# Acoustics_Board_Power.net
KiCad netlist of a schematic drawn in Altium Designer
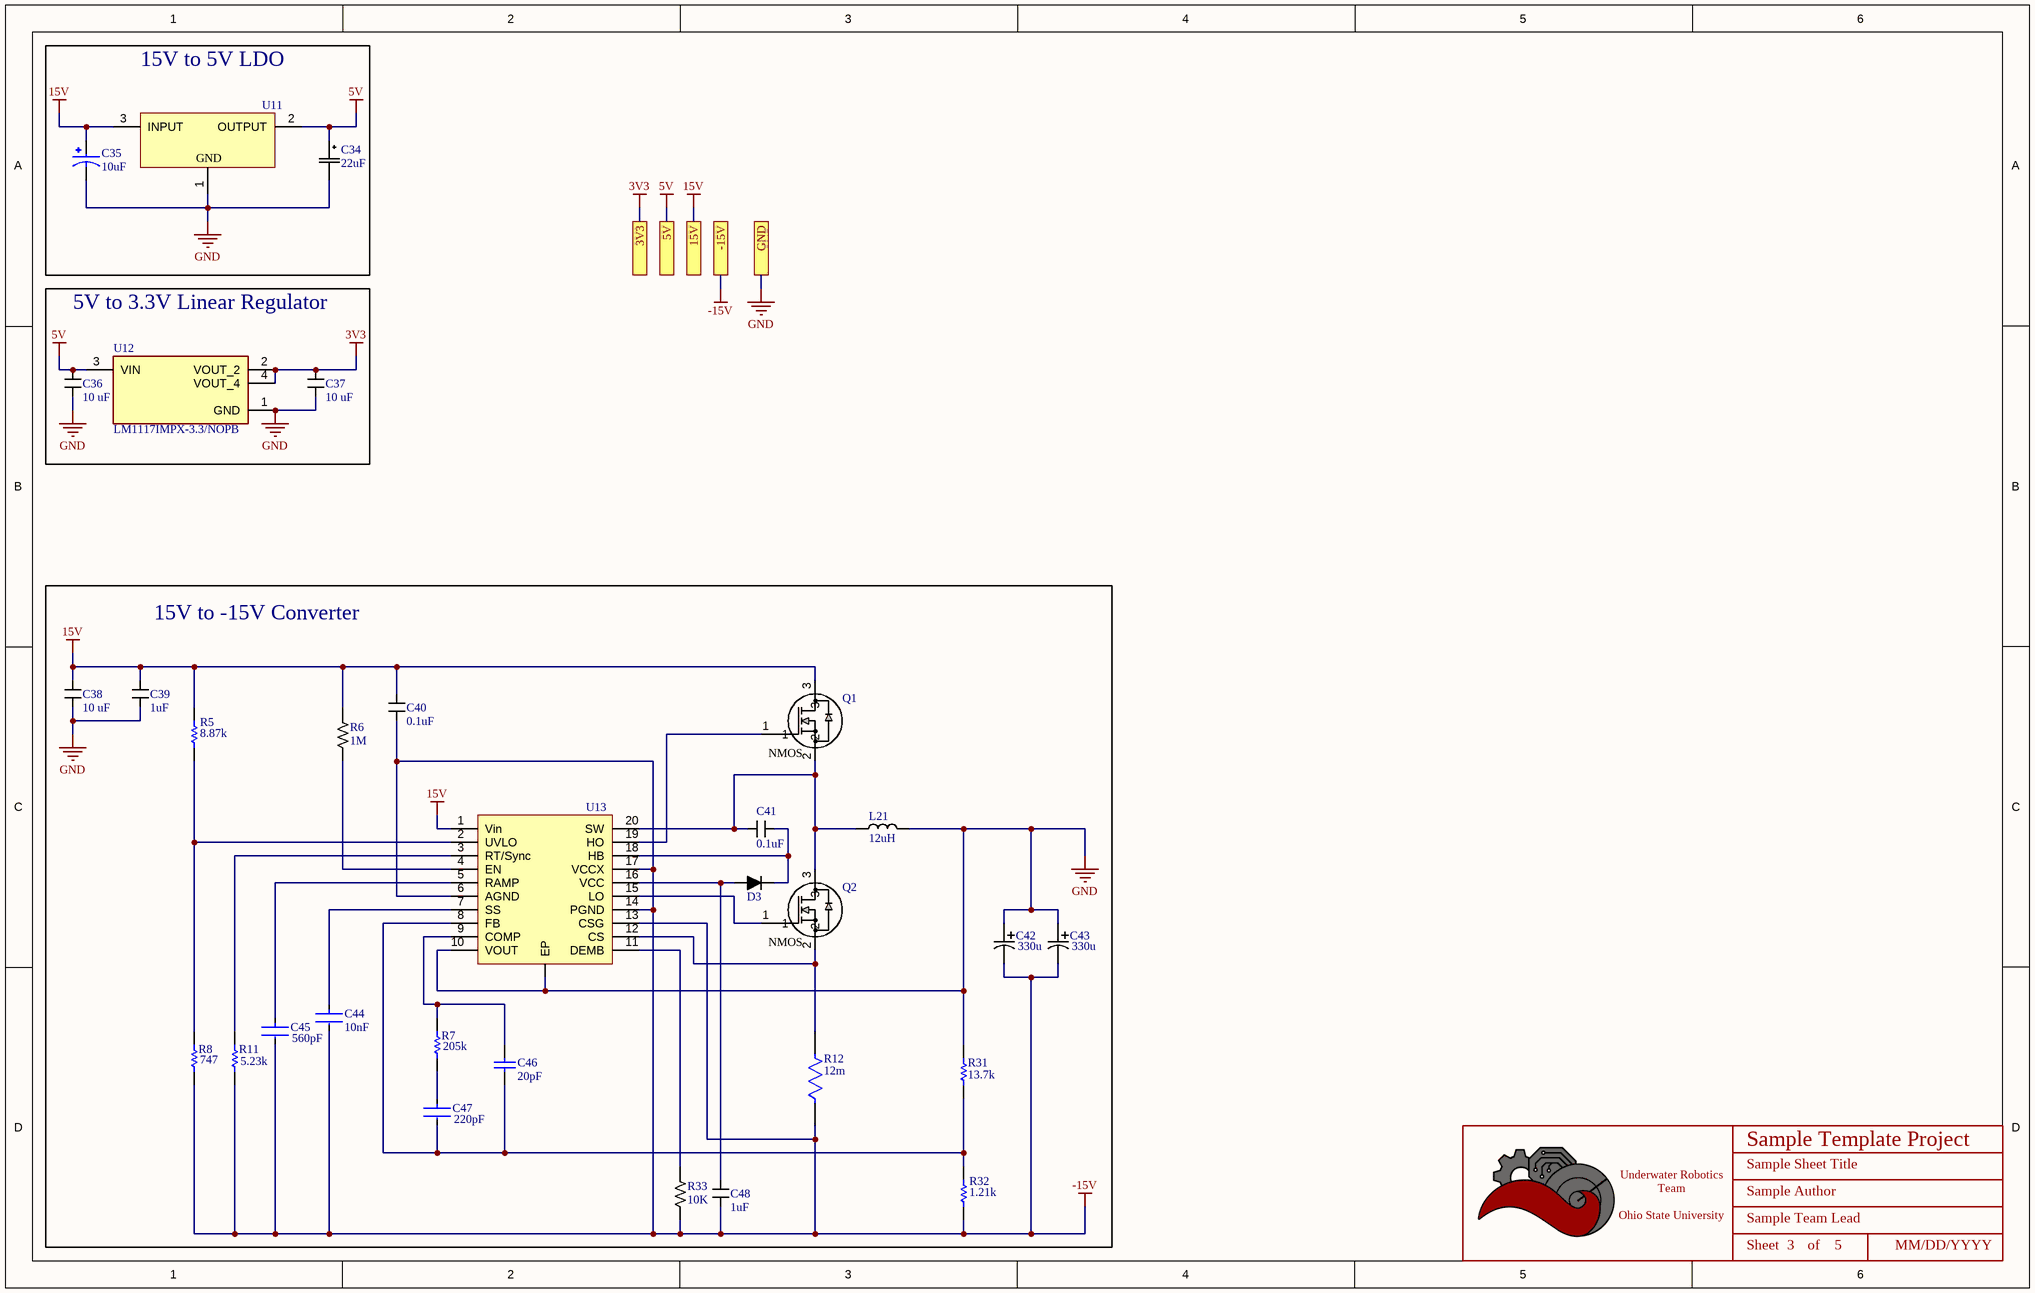
[diagram p0: Acoustics Board Power.SchDoc]

(export (version "E")
  (design (tool "Eeschema 10.0.6"))
  (components
    (comp (ref "C34")
      (value "22uF")
      (footprint "PCAP_8x5.4-ELECT_NCA")
      (description "22 µF 35 V Aluminum Electrolytic Capacitors Radial, Can - SMD 1000 Hrs")
      (fields
        (field (name "VOLTAGE") "35V")
        (field (name "Comment") "22uF electrolytic 35 V")
        (field (name "MADE BY") "Robert Pafford")
      )
      (libsource (lib "Capacitors") (part "CAP ALUM 22UF 20% 35V SMD"))
    )
    (comp (ref "C35")
      (value "10uF")
      (footprint "CAP_EEHZC1J100P")
      (description "10 µF 63 V Aluminum - Polymer Capacitors Radial, Can SMD 120mOhm")
      (fields
        (field (name "TOLERANCE") "+/- 20%")
        (field (name "Comment") "10uF electrolytic 63V")
        (field (name "MADE BY") "Robert Pafford")
      )
      (libsource (lib "Capacitors") (part "CAP ALUM 10UF 20% 63V SMD"))
    )
    (comp (ref "C36")
      (value "10uF Ceramic 6.3V")
      (footprint "CAPACITOR_0603")
      (description "Cap 10uF 6.3V +/-20%\r\nCeramic 0603")
      (fields
        (field (name "TOLERANCE") "+/- 20%")
        (field (name "VOLTAGE") "6.3V")
        (field (name "VALUE (UF)") "10 uF")
        (field (name "MADE BY") "Flip B")
      )
      (libsource (lib "Capacitors") (part "CAPACITOR_10uF_0603"))
    )
    (comp (ref "C37")
      (value "10uF Ceramic 6.3V")
      (footprint "CAPACITOR_0603")
      (description "Cap 10uF 6.3V +/-20%\r\nCeramic 0603")
      (fields
        (field (name "TOLERANCE") "+/- 20%")
        (field (name "VOLTAGE") "6.3V")
        (field (name "VALUE (UF)") "10 uF")
        (field (name "MADE BY") "Flip B")
      )
      (libsource (lib "Capacitors") (part "CAPACITOR_10uF_0603"))
    )
    (comp (ref "C38")
      (value "10uF Ceramic 6.3V")
      (footprint "CAPACITOR_0603")
      (description "Cap 10uF 6.3V +/-20%\r\nCeramic 0603")
      (fields
        (field (name "TOLERANCE") "+/- 20%")
        (field (name "VOLTAGE") "6.3V")
        (field (name "VALUE (UF)") "10 uF")
        (field (name "MADE BY") "Flip B")
      )
      (libsource (lib "Capacitors") (part "CAPACITOR_10uF_0603"))
    )
    (comp (ref "C39")
      (value "1uF")
      (footprint "CAPACITOR_0402")
      (description "Cap 1uF 16V +/-10%\r\nCeramic 0402")
      (fields
        (field (name "TOLERANCE") "+/- 10%")
        (field (name "VOLTAGE") "16V")
        (field (name "MADE BY") "Robert Pafford")
      )
      (libsource (lib "Capacitors") (part "CAPACITOR_1uF_0402"))
    )
    (comp (ref "C40")
      (value "0.1uF")
      (footprint "CAPACITOR_0402")
      (description "Cap 100nF 25V +/-10%\r\nCeramic 0402")
      (fields
        (field (name "TOLERANCE") "+/- 10%")
        (field (name "VOLTAGE") "25V")
        (field (name "MADE BY") "Robert Pafford")
      )
      (libsource (lib "Capacitors") (part "CAPACITOR_0.1uF_0402"))
    )
    (comp (ref "C41")
      (value "0.1uF")
      (footprint "CAPACITOR_0402")
      (description "Cap 100nF 25V +/-10%\r\nCeramic 0402")
      (fields
        (field (name "TOLERANCE") "+/- 10%")
        (field (name "VOLTAGE") "25V")
        (field (name "MADE BY") "Robert Pafford")
      )
      (libsource (lib "Capacitors") (part "CAPACITOR_0.1uF_0402"))
    )
    (comp (ref "C42")
      (value "EEH-ZC1E331P")
      (footprint "PCAP_EEHZ_G_PAN")
      (description "No Description Available")
      (fields
        (field (name "CAPACITANCE") "330u")
        (field (name "COPYRIGHT") "Copyright (C) 2024 Ultra Librarian. All rights reserved.")
      )
      (libsource (lib "Capacitors") (part "EEH-ZC1E331P"))
    )
    (comp (ref "C43")
      (value "EEH-ZC1E331P")
      (footprint "PCAP_EEHZ_G_PAN")
      (description "No Description Available")
      (fields
        (field (name "CAPACITANCE") "330u")
        (field (name "COPYRIGHT") "Copyright (C) 2024 Ultra Librarian. All rights reserved.")
      )
      (libsource (lib "Capacitors") (part "EEH-ZC1E331P"))
    )
    (comp (ref "C44")
      (value "10nF")
      (footprint "CAPACITOR_0402")
      (description "CAP CER 10000PF 50V X7R 0402")
      (fields
        (field (name "OCTOPART") "https://octopart.com/cc0402krx7r9bb103-yageo-8376513")
        (field (name "MANUFACTURER PART NUMBER") "CC0402KRX7R9BB103")
      )
      (libsource (lib "Capacitors") (part "CAP CER 0.01 UF 0402"))
    )
    (comp (ref "C45")
      (value "CL10C221JB8NNNC")
      (footprint "FP-CL10-IPC_C")
      (description "Cap Ceramic 220pF 50V C0G ±5% Pad SMD 0603 +125°C T/R")
      (fields
        (field (name "VOLTAGE") "50V")
        (field (name "CAPACITANCE") "560pF")
        (field (name "TOLERANCE") "5%")
      )
      (libsource (lib "Altium Content Vault") (part "b4654b650e69147ec39a6b967a45e02"))
    )
    (comp (ref "C46")
      (value "CL10C200JB8NNNC")
      (footprint "CAPC1608X90X30LL10T20")
      (description "Chip Capacitor, 20 pF, +/- 5%, 50 V, -55 to 85 degC, 0603 (1608 Metric), RoHS, Tape and Reel")
      (fields (field (name "MANUFACTURER") "Samsung Electro-Mechanics") (field (name "CAPACITANCE") "20pF"))
      (libsource (lib "Altium Content Vault") (part "CAP-NP-2"))
    )
    (comp (ref "C47")
      (value "CL10C221JB8NNNC")
      (footprint "FP-CL10-IPC_C")
      (description "Cap Ceramic 220pF 50V C0G ±5% Pad SMD 0603 +125°C T/R")
      (fields
        (field (name "VOLTAGE") "50V")
        (field (name "CAPACITANCE") "220pF")
        (field (name "TOLERANCE") "5%")
      )
      (libsource (lib "Altium Content Vault") (part "b4654b650e69147ec39a6b967a45e02"))
    )
    (comp (ref "C48")
      (value "1uF")
      (footprint "CAPACITOR_0402")
      (description "Cap 1uF 16V +/-10%\r\nCeramic 0402")
      (fields
        (field (name "TOLERANCE") "+/- 10%")
        (field (name "VOLTAGE") "16V")
        (field (name "MADE BY") "Robert Pafford")
      )
      (libsource (lib "Capacitors") (part "CAPACITOR_1uF_0402"))
    )
    (comp (ref "D3")
      (value "B330-13-F")
      (footprint "DO-214AB")
      (description "Schottky Diode, 30V reverse breakdown, 3A, Vf = 0.500V")
      (fields (field (name "MADE BY") "Tyson N."))
      (libsource (lib "Diodes") (part "SCHOTTKY_30V_3A"))
    )
    (comp (ref "L21")
      (value "12uH")
      (footprint "INDUCTOR_0603")
      (description "12 µH Shielded Multilayer Inductor 10 mA 1.8Ohm Max 0603 (1608 Metric)")
      (fields
        (field (name "TOLERANCE") "+/- 20%")
        (field (name "Comment") "FIXED IND 12UH 10MA 1.8 OHM SMD")
        (field (name "MADE BY") "Robert Pafford")
      )
      (libsource (lib "Inductors") (part "INDUCTOR_12uH_0603"))
    )
    (comp (ref "Q1")
      (value "MOSFET N-Ch 80V 100A D2PAK")
      (footprint "D2PAK")
      (description "N-Channel 80V 100A (Ta) 306W (Ta), Surface Mount D2PAK")
      (fields
        (field (name "MANUFACTURER _PART_NUMBER") "PSMN4R4-80BS,118")
        (field (name "CREATED BY") "Flip B")
      )
      (libsource (lib "Transistors") (part "PSMN4R4-80BS,118"))
    )
    (comp (ref "Q2")
      (value "MOSFET N-Ch 80V 100A D2PAK")
      (footprint "D2PAK")
      (description "N-Channel 80V 100A (Ta) 306W (Ta), Surface Mount D2PAK")
      (fields
        (field (name "MANUFACTURER _PART_NUMBER") "PSMN4R4-80BS,118")
        (field (name "CREATED BY") "Flip B")
      )
      (libsource (lib "Transistors") (part "PSMN4R4-80BS,118"))
    )
    (comp (ref "R5")
      (value "RC0603FR-078K87L")
      (footprint "RESC1608X55X25LL10T15")
      (fields
        (field (name "MANUFACTURER") "Yageo")
        (field (name "PART NUMBER") "RC0603FR-071K21L")
        (field (name "RESISTANCE") "8.87k")
      )
      (libsource (lib "Altium Content Vault") (part "RES"))
    )
    (comp (ref "R6")
      (value "1M Ohm 1% 1/16W")
      (footprint "RESISTOR_0402")
      (description "RES 1M OHM 1% 1/16W 0402")
      (fields
        (field (name "TOLERANCE") "+/- 1%")
        (field (name "VALUE  (OHMS)") "1M")
        (field (name "MADE BY") "Robert Pafford")
      )
      (libsource (lib "Resistors") (part "RESISTOR_1M_0402"))
    )
    (comp (ref "R7")
      (value "RC0402FR-07205KL")
      (footprint "RESC1005X40X25ML05T10")
      (fields (field (name "MANUFACTURER") "Yageo / Phycomp") (field (name "RESISTANCE") "205k"))
      (libsource (lib "Altium Content Vault") (part "RES"))
    )
    (comp (ref "R8")
      (value "CRCW0603787RFKEA")
      (footprint "RESC1609X50X30NL10T20")
      (fields (field (name "MANUFACTURER") "Vishay Dale") (field (name "RESISTANCE") "747"))
      (libsource (lib "Altium Content Vault") (part "RES"))
    )
    (comp (ref "R11")
      (value "RC0402FR-075K23L")
      (footprint "RESC1005X40X25NL05T10")
      (fields (field (name "MANUFACTURER") "Yageo") (field (name "RESISTANCE") "5.23k"))
      (libsource (lib "Altium Content Vault") (part "RES"))
    )
    (comp (ref "R12")
      (value "CSR1206FK12L0")
      (footprint "FP-CSR1206-IPC_B")
      (description "General Purpose Thick Film Chip Resistor, 1206, 12mΩ, 1%, 0.5W")
      (fields (field (name "TOLERANCE") "1%") (field (name "RESISTANCE") "12m"))
      (libsource (lib "Altium Content Vault") (part "1029c3af85768c4190bb7ad29bc67b5"))
    )
    (comp (ref "R31")
      (value "CRCW060313K7FKEA")
      (footprint "RESC1609X50X30ML10T20")
      (fields (field (name "MANUFACTURER") "Vishay Dale") (field (name "RESISTANCE") "13.7k"))
      (libsource (lib "Altium Content Vault") (part "RES"))
    )
    (comp (ref "R32")
      (value "RC0603FR-071K21L")
      (footprint "RESC1608X55X25LL10T15")
      (fields (field (name "MANUFACTURER") "Yageo") (field (name "RESISTANCE") "1.21k"))
      (libsource (lib "Altium Content Vault") (part "RES"))
    )
    (comp (ref "R33")
      (value "10k Ohm 0.5% 1/10W")
      (footprint "RESISTOR_0603")
      (description "RES 10k OHM 0.5% 1/10W 0603")
      (fields
        (field (name "TOLERANCE") "+/- 0.5%")
        (field (name "VALUE  (OHMS)") "10K")
        (field (name "MADE BY") "Robert Pafford")
      )
      (libsource (lib "Resistors") (part "RESISTOR_10K_0.5%_0603"))
    )
    (comp (ref "U11")
      (value "AZ1117IH-5.0TRG1")
      (footprint "SOT223-3")
      (description "Linear Voltage Regulator IC Positive Fixed 1 Output 1A SOT-223-3")
      (libsource (lib "Integrated Circuits") (part "AZ1117IH-5.0TRG1"))
    )
    (comp (ref "U12")
      (value "LM1117IMPX-3.3/NOPB")
      (footprint "SOT-223-4")
      (description "800-mA 15-V linear voltage regulator 4-SOT-223 -40 to 125")
      (fields (field (name "MF") "Texas Instruments"))
      (libsource (lib "Integrated Circuits") (part "LM1117IMPX-3.3/NOPB"))
    )
    (comp (ref "U13")
      (value "LM25116")
      (footprint "LM25116")
      (description "IC REG CTRLR BUCK 20TSSOP")
      (libsource (lib "Integrated Circuits") (part "LM25116"))
    )
  )
  (nets
    (net (code "1") (name "-15V") (class "Default")
      (node (ref "C40") (pin "2") (pinfunction "2_2") (pintype "passive"))
      (node (ref "C42") (pin "2") (pinfunction "2_2") (pintype "passive"))
      (node (ref "C43") (pin "2") (pinfunction "2_2") (pintype "passive"))
      (node (ref "C44") (pin "2") (pinfunction "2_2") (pintype "passive"))
      (node (ref "C45") (pin "2") (pinfunction "2_2") (pintype "passive"))
      (node (ref "C48") (pin "2") (pinfunction "2_2") (pintype "passive"))
      (node (ref "R11") (pin "1") (pinfunction "1_1") (pintype "passive"))
      (node (ref "R12") (pin "1") (pinfunction "1_1") (pintype "passive"))
      (node (ref "R32") (pin "2") (pinfunction "2_2") (pintype "passive"))
      (node (ref "R33") (pin "2") (pinfunction "2_2") (pintype "passive"))
      (node (ref "R8") (pin "1") (pinfunction "1_1") (pintype "passive"))
      (node (ref "U13") (pin "13") (pinfunction "CSG_13") (pintype "passive"))
      (node (ref "U13") (pin "14") (pinfunction "PGND_14") (pintype "passive"))
      (node (ref "U13") (pin "17") (pinfunction "VCCX_17") (pintype "passive"))
      (node (ref "U13") (pin "6") (pinfunction "AGND_6") (pintype "passive"))
    )
    (net (code "2") (name "3V3") (class "Default")
      (node (ref "C37") (pin "1") (pinfunction "1_1") (pintype "passive"))
      (node (ref "U12") (pin "2") (pinfunction "VOUT_2_2") (pintype "power_in"))
      (node (ref "U12") (pin "4") (pinfunction "VOUT_4_4") (pintype "power_in"))
    )
    (net (code "3") (name "5V") (class "Default")
      (node (ref "C34") (pin "1") (pinfunction "1_1") (pintype "passive"))
      (node (ref "C36") (pin "1") (pinfunction "1_1") (pintype "passive"))
      (node (ref "U11") (pin "2") (pinfunction "OUTPUT_2") (pintype "passive"))
      (node (ref "U12") (pin "3") (pinfunction "VIN_3") (pintype "power_in"))
    )
    (net (code "4") (name "15V") (class "Default")
      (node (ref "C35") (pin "1") (pinfunction "1_1") (pintype "passive"))
      (node (ref "C38") (pin "1") (pinfunction "1_1") (pintype "passive"))
      (node (ref "C39") (pin "1") (pinfunction "1_1") (pintype "passive"))
      (node (ref "C40") (pin "1") (pinfunction "1_1") (pintype "passive"))
      (node (ref "Q1") (pin "3") (pinfunction "3_3") (pintype "passive"))
      (node (ref "R5") (pin "1") (pinfunction "1_1") (pintype "passive"))
      (node (ref "R6") (pin "1") (pinfunction "1_1") (pintype "passive"))
      (node (ref "U11") (pin "3") (pinfunction "INPUT_3") (pintype "passive"))
      (node (ref "U13") (pin "1") (pinfunction "Vin_1") (pintype "passive"))
    )
    (net (code "5") (name "GND") (class "Default")
      (node (ref "C34") (pin "2") (pinfunction "2_2") (pintype "passive"))
      (node (ref "C35") (pin "2") (pinfunction "2_2") (pintype "passive"))
      (node (ref "C36") (pin "2") (pinfunction "2_2") (pintype "passive"))
      (node (ref "C37") (pin "2") (pinfunction "2_2") (pintype "passive"))
      (node (ref "C38") (pin "2") (pinfunction "2_2") (pintype "passive"))
      (node (ref "C39") (pin "2") (pinfunction "2_2") (pintype "passive"))
      (node (ref "C42") (pin "1") (pinfunction "1_1") (pintype "passive"))
      (node (ref "C43") (pin "1") (pinfunction "1_1") (pintype "passive"))
      (node (ref "L21") (pin "1") (pinfunction "1_1") (pintype "passive"))
      (node (ref "R31") (pin "2") (pinfunction "2_2") (pintype "passive"))
      (node (ref "U11") (pin "1") (pinfunction "GND_1") (pintype "passive"))
      (node (ref "U12") (pin "1") (pinfunction "GND_1") (pintype "power_in"))
      (node (ref "U13") (pin "10") (pinfunction "VOUT_10") (pintype "passive"))
      (node (ref "U13") (pin "21") (pinfunction "EP_21") (pintype "passive"))
    )
    (net (code "6") (name "Net-(C47-Pad1)") (class "Default")
      (node (ref "C47") (pin "1") (pinfunction "1_1") (pintype "passive"))
      (node (ref "R7") (pin "1") (pinfunction "1_1") (pintype "passive"))
    )
    (net (code "7") (name "Net-(U13-COMP)") (class "Default")
      (node (ref "C46") (pin "1") (pinfunction "1_1") (pintype "passive"))
      (node (ref "R7") (pin "2") (pinfunction "2_2") (pintype "passive"))
      (node (ref "U13") (pin "9") (pinfunction "COMP_9") (pintype "passive"))
    )
    (net (code "8") (name "Net-(U13-CS)") (class "Default")
      (node (ref "Q2") (pin "2") (pinfunction "2_2") (pintype "passive"))
      (node (ref "R12") (pin "2") (pinfunction "2_2") (pintype "passive"))
      (node (ref "U13") (pin "12") (pinfunction "CS_12") (pintype "passive"))
    )
    (net (code "9") (name "Net-(U13-DEMB)") (class "Default")
      (node (ref "R33") (pin "1") (pinfunction "1_1") (pintype "passive"))
      (node (ref "U13") (pin "11") (pinfunction "DEMB_11") (pintype "passive"))
    )
    (net (code "10") (name "Net-(U13-EN)") (class "Default")
      (node (ref "R6") (pin "2") (pinfunction "2_2") (pintype "passive"))
      (node (ref "U13") (pin "4") (pinfunction "EN_4") (pintype "passive"))
    )
    (net (code "11") (name "Net-(U13-FB)") (class "Default")
      (node (ref "C46") (pin "2") (pinfunction "2_2") (pintype "passive"))
      (node (ref "C47") (pin "2") (pinfunction "2_2") (pintype "passive"))
      (node (ref "R31") (pin "1") (pinfunction "1_1") (pintype "passive"))
      (node (ref "R32") (pin "1") (pinfunction "1_1") (pintype "passive"))
      (node (ref "U13") (pin "8") (pinfunction "FB_8") (pintype "passive"))
    )
    (net (code "12") (name "Net-(U13-HB)") (class "Default")
      (node (ref "C41") (pin "2") (pinfunction "2_2") (pintype "passive"))
      (node (ref "D3") (pin "2") (pinfunction "2_2") (pintype "passive"))
      (node (ref "U13") (pin "18") (pinfunction "HB_18") (pintype "passive"))
    )
    (net (code "13") (name "Net-(U13-HO)") (class "Default")
      (node (ref "Q1") (pin "1") (pinfunction "1_1") (pintype "passive"))
      (node (ref "U13") (pin "19") (pinfunction "HO_19") (pintype "passive"))
    )
    (net (code "14") (name "Net-(U13-LO)") (class "Default")
      (node (ref "Q2") (pin "1") (pinfunction "1_1") (pintype "passive"))
      (node (ref "U13") (pin "15") (pinfunction "LO_15") (pintype "passive"))
    )
    (net (code "15") (name "Net-(U13-RAMP)") (class "Default")
      (node (ref "C45") (pin "1") (pinfunction "1_1") (pintype "passive"))
      (node (ref "U13") (pin "5") (pinfunction "RAMP_5") (pintype "passive"))
    )
    (net (code "16") (name "Net-(U13-RT{slash}Sync)") (class "Default")
      (node (ref "R11") (pin "2") (pinfunction "2_2") (pintype "passive"))
      (node (ref "U13") (pin "3") (pinfunction "RT/Sync_3") (pintype "passive"))
    )
    (net (code "17") (name "Net-(U13-SS)") (class "Default")
      (node (ref "C44") (pin "1") (pinfunction "1_1") (pintype "passive"))
      (node (ref "U13") (pin "7") (pinfunction "SS_7") (pintype "passive"))
    )
    (net (code "18") (name "Net-(U13-SW)") (class "Default")
      (node (ref "C41") (pin "1") (pinfunction "1_1") (pintype "passive"))
      (node (ref "L21") (pin "2") (pinfunction "2_2") (pintype "passive"))
      (node (ref "Q1") (pin "2") (pinfunction "2_2") (pintype "passive"))
      (node (ref "Q2") (pin "3") (pinfunction "3_3") (pintype "passive"))
      (node (ref "U13") (pin "20") (pinfunction "SW_20") (pintype "passive"))
    )
    (net (code "19") (name "Net-(U13-UVLO)") (class "Default")
      (node (ref "R5") (pin "2") (pinfunction "2_2") (pintype "passive"))
      (node (ref "R8") (pin "2") (pinfunction "2_2") (pintype "passive"))
      (node (ref "U13") (pin "2") (pinfunction "UVLO_2") (pintype "passive"))
    )
    (net (code "20") (name "Net-(U13-VCC)") (class "Default")
      (node (ref "C48") (pin "1") (pinfunction "1_1") (pintype "passive"))
      (node (ref "D3") (pin "1") (pinfunction "1_1") (pintype "passive"))
      (node (ref "U13") (pin "16") (pinfunction "VCC_16") (pintype "passive"))
    )
  )
)
